# Frontend.net
KiCad netlist of a schematic drawn in Altium Designer
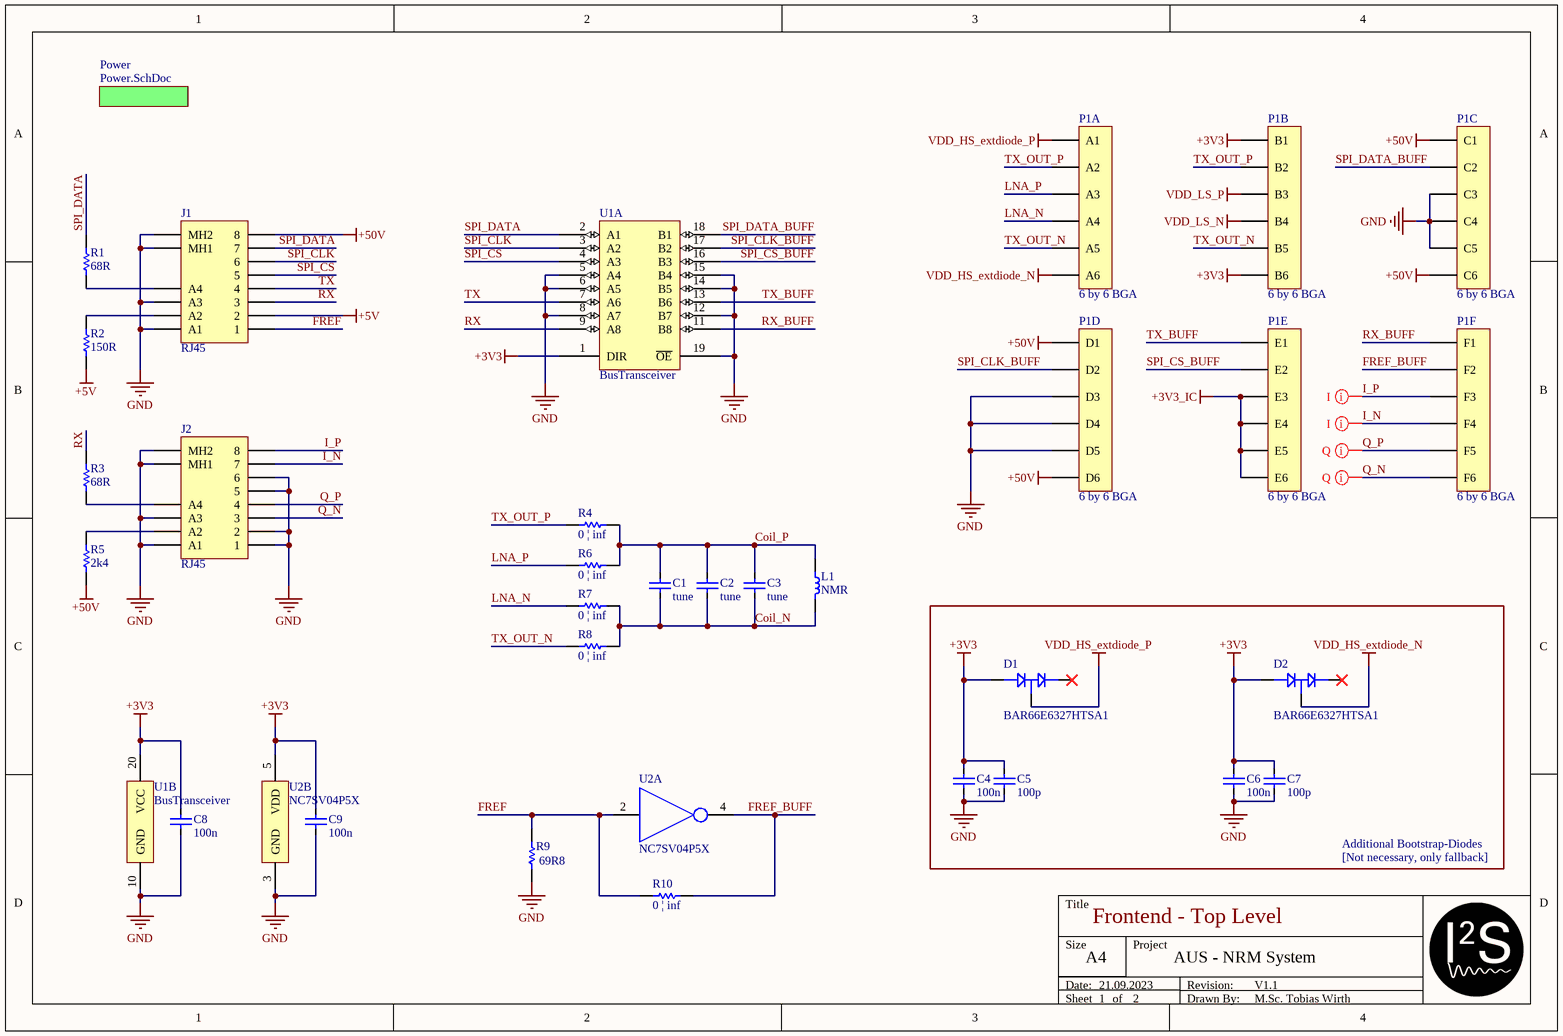
[diagram p0: Frontend.SchDoc]

(export (version "E")
  (design (tool "Eeschema 10.0.6"))
  (components
    (comp (ref "C1") (value "tune") (footprint "CAP_1206") (libsource (lib "IIS-Lib_TW") (part "Cap")))
    (comp (ref "C2") (value "tune") (footprint "CAP_0805") (libsource (lib "IIS-Lib_TW") (part "Cap")))
    (comp (ref "C3") (value "tune") (footprint "CAP_0603") (libsource (lib "IIS-Lib_TW") (part "Cap")))
    (comp (ref "C4") (value "100n") (footprint "CAP_0603") (libsource (lib "IIS-Lib_TW") (part "Cap")))
    (comp (ref "C5") (value "100p") (footprint "CAP_0603") (libsource (lib "IIS-Lib_TW") (part "Cap")))
    (comp (ref "C6") (value "100n") (footprint "CAP_0603") (libsource (lib "IIS-Lib_TW") (part "Cap")))
    (comp (ref "C7") (value "100p") (footprint "CAP_0603") (libsource (lib "IIS-Lib_TW") (part "Cap")))
    (comp (ref "C8") (value "100n") (footprint "CAP_0603") (libsource (lib "IIS-Lib_TW") (part "Cap")))
    (comp (ref "C9") (value "100n") (footprint "CAP_0603") (libsource (lib "IIS-Lib_TW") (part "Cap")))
    (comp (ref "D1")
      (value "BAR66E6327HTSA1")
      (footprint "SOT23")
      (description "SMP1320-075LF (SC-70)\r\nBAV99 (SOT23)")
      (libsource (lib "IIS-Lib_TW") (part "Diode_series"))
    )
    (comp (ref "D2")
      (value "BAR66E6327HTSA1")
      (footprint "SOT23")
      (description "SMP1320-075LF (SC-70)\r\nBAV99 (SOT23)")
      (libsource (lib "IIS-Lib_TW") (part "Diode_series"))
    )
    (comp (ref "J1")
      (value "RJ45")
      (footprint "RJ45 - RJE3A1880412")
      (description "Ethernet Connectors RJ45 SMT")
      (libsource (lib "IIS-Lib_TW") (part "RJ45"))
    )
    (comp (ref "J2")
      (value "RJ45")
      (footprint "RJ45 - RJE3A1880412")
      (description "Ethernet Connectors RJ45 SMT")
      (libsource (lib "IIS-Lib_TW") (part "RJ45"))
    )
    (comp (ref "L1") (value "NMR") (footprint "NMR-Coil-Pads") (libsource (lib "IIS-Lib_TW") (part "Ind")))
    (comp (ref "P1")
      (value "6 by 6 BGA")
      (footprint "BGA36C230P6X6_1500X1500X190 - Interposer")
      (libsource (lib "IIS-Lib_TW") (part "BGA_6x6"))
    )
    (comp (ref "R1") (value "68R") (footprint "RES_0603") (libsource (lib "IIS-Lib_TW") (part "Res")))
    (comp (ref "R2") (value "150R") (footprint "RES_0603") (libsource (lib "IIS-Lib_TW") (part "Res")))
    (comp (ref "R3") (value "68R") (footprint "RES_0603") (libsource (lib "IIS-Lib_TW") (part "Res")))
    (comp (ref "R4") (value "0 ¦ inf") (footprint "RES_0603") (libsource (lib "IIS-Lib_TW") (part "Res")))
    (comp (ref "R5") (value "2k4") (footprint "RES_0603") (libsource (lib "IIS-Lib_TW") (part "Res")))
    (comp (ref "R6") (value "0 ¦ inf") (footprint "RES_0603") (libsource (lib "IIS-Lib_TW") (part "Res")))
    (comp (ref "R7") (value "0 ¦ inf") (footprint "RES_0603") (libsource (lib "IIS-Lib_TW") (part "Res")))
    (comp (ref "R8") (value "0 ¦ inf") (footprint "RES_0603") (libsource (lib "IIS-Lib_TW") (part "Res")))
    (comp (ref "R9") (value "69R8") (footprint "RES_0603") (libsource (lib "IIS-Lib_TW") (part "Res")))
    (comp (ref "R10") (value "0 ¦ inf") (footprint "RES_0603") (libsource (lib "IIS-Lib_TW") (part "Res")))
    (comp (ref "U1")
      (value "BusTransceiver")
      (footprint "TSSOP-20")
      (libsource (lib "IIS-Lib_TW") (part "74LVC245A"))
    )
    (comp (ref "U2")
      (value "NC7SV04P5X")
      (footprint "SOT23-65P210X110-5N")
      (libsource (lib "IIS-Lib_TW") (part "NC7SV04P5X"))
    )
  )
  (nets
    (net (code "1") (name "+3V3") (class "Default")
      (node (ref "C4") (pin "1") (pinfunction "1_1") (pintype "passive"))
      (node (ref "C5") (pin "1") (pinfunction "1_1") (pintype "passive"))
      (node (ref "C6") (pin "1") (pinfunction "1_1") (pintype "passive"))
      (node (ref "C7") (pin "1") (pinfunction "1_1") (pintype "passive"))
      (node (ref "C8") (pin "1") (pinfunction "1_1") (pintype "passive"))
      (node (ref "C9") (pin "1") (pinfunction "1_1") (pintype "passive"))
      (node (ref "D1") (pin "1") (pinfunction "1_1") (pintype "passive"))
      (node (ref "D2") (pin "1") (pinfunction "1_1") (pintype "passive"))
      (node (ref "P1") (pin "B1") (pinfunction "B1_B1") (pintype "passive"))
      (node (ref "P1") (pin "B6") (pinfunction "B6_B6") (pintype "passive"))
      (node (ref "U1") (pin "1") (pinfunction "DIR_1") (pintype "passive"))
      (node (ref "U1") (pin "20") (pinfunction "VCC_20") (pintype "passive"))
      (node (ref "U2") (pin "5") (pinfunction "VDD_5") (pintype "passive"))
    )
    (net (code "2") (name "+3V3_IC") (class "Default")
      (node (ref "P1") (pin "E3") (pinfunction "E3_E3") (pintype "passive"))
      (node (ref "P1") (pin "E4") (pinfunction "E4_E4") (pintype "passive"))
      (node (ref "P1") (pin "E5") (pinfunction "E5_E5") (pintype "passive"))
      (node (ref "P1") (pin "E6") (pinfunction "E6_E6") (pintype "passive"))
    )
    (net (code "3") (name "+5V") (class "Default")
      (node (ref "J1") (pin "2") (pinfunction "2_2") (pintype "passive"))
      (node (ref "R2") (pin "2") (pinfunction "2_2") (pintype "passive"))
    )
    (net (code "4") (name "+50V") (class "Default")
      (node (ref "J1") (pin "8") (pinfunction "8_8") (pintype "passive"))
      (node (ref "P1") (pin "C1") (pinfunction "C1_C1") (pintype "passive"))
      (node (ref "P1") (pin "C6") (pinfunction "C6_C6") (pintype "passive"))
      (node (ref "P1") (pin "D1") (pinfunction "D1_D1") (pintype "passive"))
      (node (ref "P1") (pin "D6") (pinfunction "D6_D6") (pintype "passive"))
      (node (ref "R5") (pin "2") (pinfunction "2_2") (pintype "passive"))
    )
    (net (code "5") (name "/Coil_N") (class "Default")
      (node (ref "C1") (pin "2") (pinfunction "2_2") (pintype "passive"))
      (node (ref "C2") (pin "2") (pinfunction "2_2") (pintype "passive"))
      (node (ref "C3") (pin "2") (pinfunction "2_2") (pintype "passive"))
      (node (ref "L1") (pin "2") (pinfunction "2_2") (pintype "passive"))
      (node (ref "R7") (pin "1") (pinfunction "1_1") (pintype "passive"))
      (node (ref "R8") (pin "1") (pinfunction "1_1") (pintype "passive"))
    )
    (net (code "6") (name "/Coil_P") (class "Default")
      (node (ref "C1") (pin "1") (pinfunction "1_1") (pintype "passive"))
      (node (ref "C2") (pin "1") (pinfunction "1_1") (pintype "passive"))
      (node (ref "C3") (pin "1") (pinfunction "1_1") (pintype "passive"))
      (node (ref "L1") (pin "1") (pinfunction "1_1") (pintype "passive"))
      (node (ref "R4") (pin "1") (pinfunction "1_1") (pintype "passive"))
      (node (ref "R6") (pin "1") (pinfunction "1_1") (pintype "passive"))
    )
    (net (code "7") (name "/FREF") (class "Default")
      (node (ref "J1") (pin "1") (pinfunction "1_1") (pintype "passive"))
      (node (ref "R10") (pin "2") (pinfunction "2_2") (pintype "passive"))
      (node (ref "R9") (pin "2") (pinfunction "2_2") (pintype "passive"))
      (node (ref "U2") (pin "2") (pinfunction "2_2") (pintype "passive"))
    )
    (net (code "8") (name "/FREF_BUFF") (class "Default")
      (node (ref "P1") (pin "F2") (pinfunction "F2_F2") (pintype "passive"))
      (node (ref "R10") (pin "1") (pinfunction "1_1") (pintype "passive"))
      (node (ref "U2") (pin "4") (pinfunction "4_4") (pintype "passive"))
    )
    (net (code "9") (name "/I_N") (class "Default")
      (node (ref "J2") (pin "7") (pinfunction "7_7") (pintype "passive"))
      (node (ref "P1") (pin "F4") (pinfunction "F4_F4") (pintype "passive"))
    )
    (net (code "10") (name "/I_P") (class "Default")
      (node (ref "J2") (pin "8") (pinfunction "8_8") (pintype "passive"))
      (node (ref "P1") (pin "F3") (pinfunction "F3_F3") (pintype "passive"))
    )
    (net (code "11") (name "/LNA_N") (class "Default")
      (node (ref "P1") (pin "A4") (pinfunction "A4_A4") (pintype "passive"))
      (node (ref "R7") (pin "2") (pinfunction "2_2") (pintype "passive"))
    )
    (net (code "12") (name "/LNA_P") (class "Default")
      (node (ref "P1") (pin "A3") (pinfunction "A3_A3") (pintype "passive"))
      (node (ref "R6") (pin "2") (pinfunction "2_2") (pintype "passive"))
    )
    (net (code "13") (name "/Q_N") (class "Default")
      (node (ref "J2") (pin "3") (pinfunction "3_3") (pintype "passive"))
      (node (ref "P1") (pin "F6") (pinfunction "F6_F6") (pintype "passive"))
    )
    (net (code "14") (name "/Q_P") (class "Default")
      (node (ref "J2") (pin "4") (pinfunction "4_4") (pintype "passive"))
      (node (ref "P1") (pin "F5") (pinfunction "F5_F5") (pintype "passive"))
    )
    (net (code "15") (name "/RX") (class "Default")
      (node (ref "J1") (pin "3") (pinfunction "3_3") (pintype "passive"))
      (node (ref "R3") (pin "1") (pinfunction "1_1") (pintype "passive"))
      (node (ref "U1") (pin "9") (pinfunction "A8_9") (pintype "bidirectional"))
    )
    (net (code "16") (name "/RX_BUFF") (class "Default")
      (node (ref "P1") (pin "F1") (pinfunction "F1_F1") (pintype "passive"))
      (node (ref "U1") (pin "11") (pinfunction "B8_11") (pintype "bidirectional"))
    )
    (net (code "17") (name "/SPI_CLK") (class "Default")
      (node (ref "J1") (pin "6") (pinfunction "6_6") (pintype "passive"))
      (node (ref "U1") (pin "3") (pinfunction "A2_3") (pintype "bidirectional"))
    )
    (net (code "18") (name "/SPI_CLK_BUFF") (class "Default")
      (node (ref "P1") (pin "D2") (pinfunction "D2_D2") (pintype "passive"))
      (node (ref "U1") (pin "17") (pinfunction "B2_17") (pintype "bidirectional"))
    )
    (net (code "19") (name "/SPI_CS") (class "Default")
      (node (ref "J1") (pin "5") (pinfunction "5_5") (pintype "passive"))
      (node (ref "U1") (pin "4") (pinfunction "A3_4") (pintype "bidirectional"))
    )
    (net (code "20") (name "/SPI_CS_BUFF") (class "Default")
      (node (ref "P1") (pin "E2") (pinfunction "E2_E2") (pintype "passive"))
      (node (ref "U1") (pin "16") (pinfunction "B3_16") (pintype "bidirectional"))
    )
    (net (code "21") (name "/SPI_DATA") (class "Default")
      (node (ref "J1") (pin "7") (pinfunction "7_7") (pintype "passive"))
      (node (ref "R1") (pin "1") (pinfunction "1_1") (pintype "passive"))
      (node (ref "U1") (pin "2") (pinfunction "A1_2") (pintype "bidirectional"))
    )
    (net (code "22") (name "/SPI_DATA_BUFF") (class "Default")
      (node (ref "P1") (pin "C2") (pinfunction "C2_C2") (pintype "passive"))
      (node (ref "U1") (pin "18") (pinfunction "B1_18") (pintype "bidirectional"))
    )
    (net (code "23") (name "/TX") (class "Default")
      (node (ref "J1") (pin "4") (pinfunction "4_4") (pintype "passive"))
      (node (ref "U1") (pin "7") (pinfunction "A6_7") (pintype "bidirectional"))
    )
    (net (code "24") (name "/TX_BUFF") (class "Default")
      (node (ref "P1") (pin "E1") (pinfunction "E1_E1") (pintype "passive"))
      (node (ref "U1") (pin "13") (pinfunction "B6_13") (pintype "bidirectional"))
    )
    (net (code "25") (name "/TX_OUT_N") (class "Default")
      (node (ref "P1") (pin "A5") (pinfunction "A5_A5") (pintype "passive"))
      (node (ref "P1") (pin "B5") (pinfunction "B5_B5") (pintype "passive"))
      (node (ref "R8") (pin "2") (pinfunction "2_2") (pintype "passive"))
    )
    (net (code "26") (name "/TX_OUT_P") (class "Default")
      (node (ref "P1") (pin "A2") (pinfunction "A2_A2") (pintype "passive"))
      (node (ref "P1") (pin "B2") (pinfunction "B2_B2") (pintype "passive"))
      (node (ref "R4") (pin "2") (pinfunction "2_2") (pintype "passive"))
    )
    (net (code "27") (name "GND") (class "Default")
      (node (ref "C4") (pin "2") (pinfunction "2_2") (pintype "passive"))
      (node (ref "C5") (pin "2") (pinfunction "2_2") (pintype "passive"))
      (node (ref "C6") (pin "2") (pinfunction "2_2") (pintype "passive"))
      (node (ref "C7") (pin "2") (pinfunction "2_2") (pintype "passive"))
      (node (ref "C8") (pin "2") (pinfunction "2_2") (pintype "passive"))
      (node (ref "C9") (pin "2") (pinfunction "2_2") (pintype "passive"))
      (node (ref "J1") (pin "A1") (pinfunction "A1_A1") (pintype "passive"))
      (node (ref "J1") (pin "A3") (pinfunction "A3_A3") (pintype "passive"))
      (node (ref "J1") (pin "MH1") (pinfunction "MH1_MH1") (pintype "passive"))
      (node (ref "J1") (pin "MH2") (pinfunction "MH2_MH2") (pintype "passive"))
      (node (ref "J2") (pin "1") (pinfunction "1_1") (pintype "passive"))
      (node (ref "J2") (pin "2") (pinfunction "2_2") (pintype "passive"))
      (node (ref "J2") (pin "5") (pinfunction "5_5") (pintype "passive"))
      (node (ref "J2") (pin "6") (pinfunction "6_6") (pintype "passive"))
      (node (ref "J2") (pin "A1") (pinfunction "A1_A1") (pintype "passive"))
      (node (ref "J2") (pin "A3") (pinfunction "A3_A3") (pintype "passive"))
      (node (ref "J2") (pin "MH1") (pinfunction "MH1_MH1") (pintype "passive"))
      (node (ref "J2") (pin "MH2") (pinfunction "MH2_MH2") (pintype "passive"))
      (node (ref "P1") (pin "C3") (pinfunction "C3_C3") (pintype "passive"))
      (node (ref "P1") (pin "C4") (pinfunction "C4_C4") (pintype "passive"))
      (node (ref "P1") (pin "C5") (pinfunction "C5_C5") (pintype "passive"))
      (node (ref "P1") (pin "D3") (pinfunction "D3_D3") (pintype "passive"))
      (node (ref "P1") (pin "D4") (pinfunction "D4_D4") (pintype "passive"))
      (node (ref "P1") (pin "D5") (pinfunction "D5_D5") (pintype "passive"))
      (node (ref "R9") (pin "1") (pinfunction "1_1") (pintype "passive"))
      (node (ref "U1") (pin "10") (pinfunction "GND_10") (pintype "passive"))
      (node (ref "U1") (pin "12") (pinfunction "B7_12") (pintype "bidirectional"))
      (node (ref "U1") (pin "14") (pinfunction "B5_14") (pintype "bidirectional"))
      (node (ref "U1") (pin "15") (pinfunction "B4_15") (pintype "bidirectional"))
      (node (ref "U1") (pin "19") (pinfunction "~{OE}_19") (pintype "passive"))
      (node (ref "U1") (pin "5") (pinfunction "A4_5") (pintype "bidirectional"))
      (node (ref "U1") (pin "6") (pinfunction "A5_6") (pintype "bidirectional"))
      (node (ref "U1") (pin "8") (pinfunction "A7_8") (pintype "bidirectional"))
      (node (ref "U2") (pin "3") (pinfunction "GND_3") (pintype "passive"))
    )
    (net (code "28") (name "Net-(J1-PadA2)") (class "Default")
      (node (ref "J1") (pin "A2") (pinfunction "A2_A2") (pintype "passive"))
      (node (ref "R2") (pin "1") (pinfunction "1_1") (pintype "passive"))
    )
    (net (code "29") (name "Net-(J1-PadA4)") (class "Default")
      (node (ref "J1") (pin "A4") (pinfunction "A4_A4") (pintype "passive"))
      (node (ref "R1") (pin "2") (pinfunction "2_2") (pintype "passive"))
    )
    (net (code "30") (name "Net-(J2-PadA2)") (class "Default")
      (node (ref "J2") (pin "A2") (pinfunction "A2_A2") (pintype "passive"))
      (node (ref "R5") (pin "1") (pinfunction "1_1") (pintype "passive"))
    )
    (net (code "31") (name "Net-(J2-PadA4)") (class "Default")
      (node (ref "J2") (pin "A4") (pinfunction "A4_A4") (pintype "passive"))
      (node (ref "R3") (pin "2") (pinfunction "2_2") (pintype "passive"))
    )
    (net (code "32") (name "VDD_HS_extdiode_N") (class "Default")
      (node (ref "D2") (pin "3") (pinfunction "3_3") (pintype "passive"))
      (node (ref "P1") (pin "A6") (pinfunction "A6_A6") (pintype "passive"))
    )
    (net (code "33") (name "VDD_HS_extdiode_P") (class "Default")
      (node (ref "D1") (pin "3") (pinfunction "3_3") (pintype "passive"))
      (node (ref "P1") (pin "A1") (pinfunction "A1_A1") (pintype "passive"))
    )
    (net (code "34") (name "VDD_LS_N") (class "Default")
      (node (ref "P1") (pin "B4") (pinfunction "B4_B4") (pintype "passive"))
    )
    (net (code "35") (name "VDD_LS_P") (class "Default")
      (node (ref "P1") (pin "B3") (pinfunction "B3_B3") (pintype "passive"))
    )
    (net (code "36") (name "unconnected-(D1-Pad2)") (class "Default")
      (node (ref "D1") (pin "2") (pinfunction "2_2") (pintype "passive+no_connect"))
    )
    (net (code "37") (name "unconnected-(D2-Pad2)") (class "Default")
      (node (ref "D2") (pin "2") (pinfunction "2_2") (pintype "passive+no_connect"))
    )
  )
)
